# SCH_n2_power_distribution_board-png_2022.net
KiCad netlist of a schematic drawn in EasyEDA
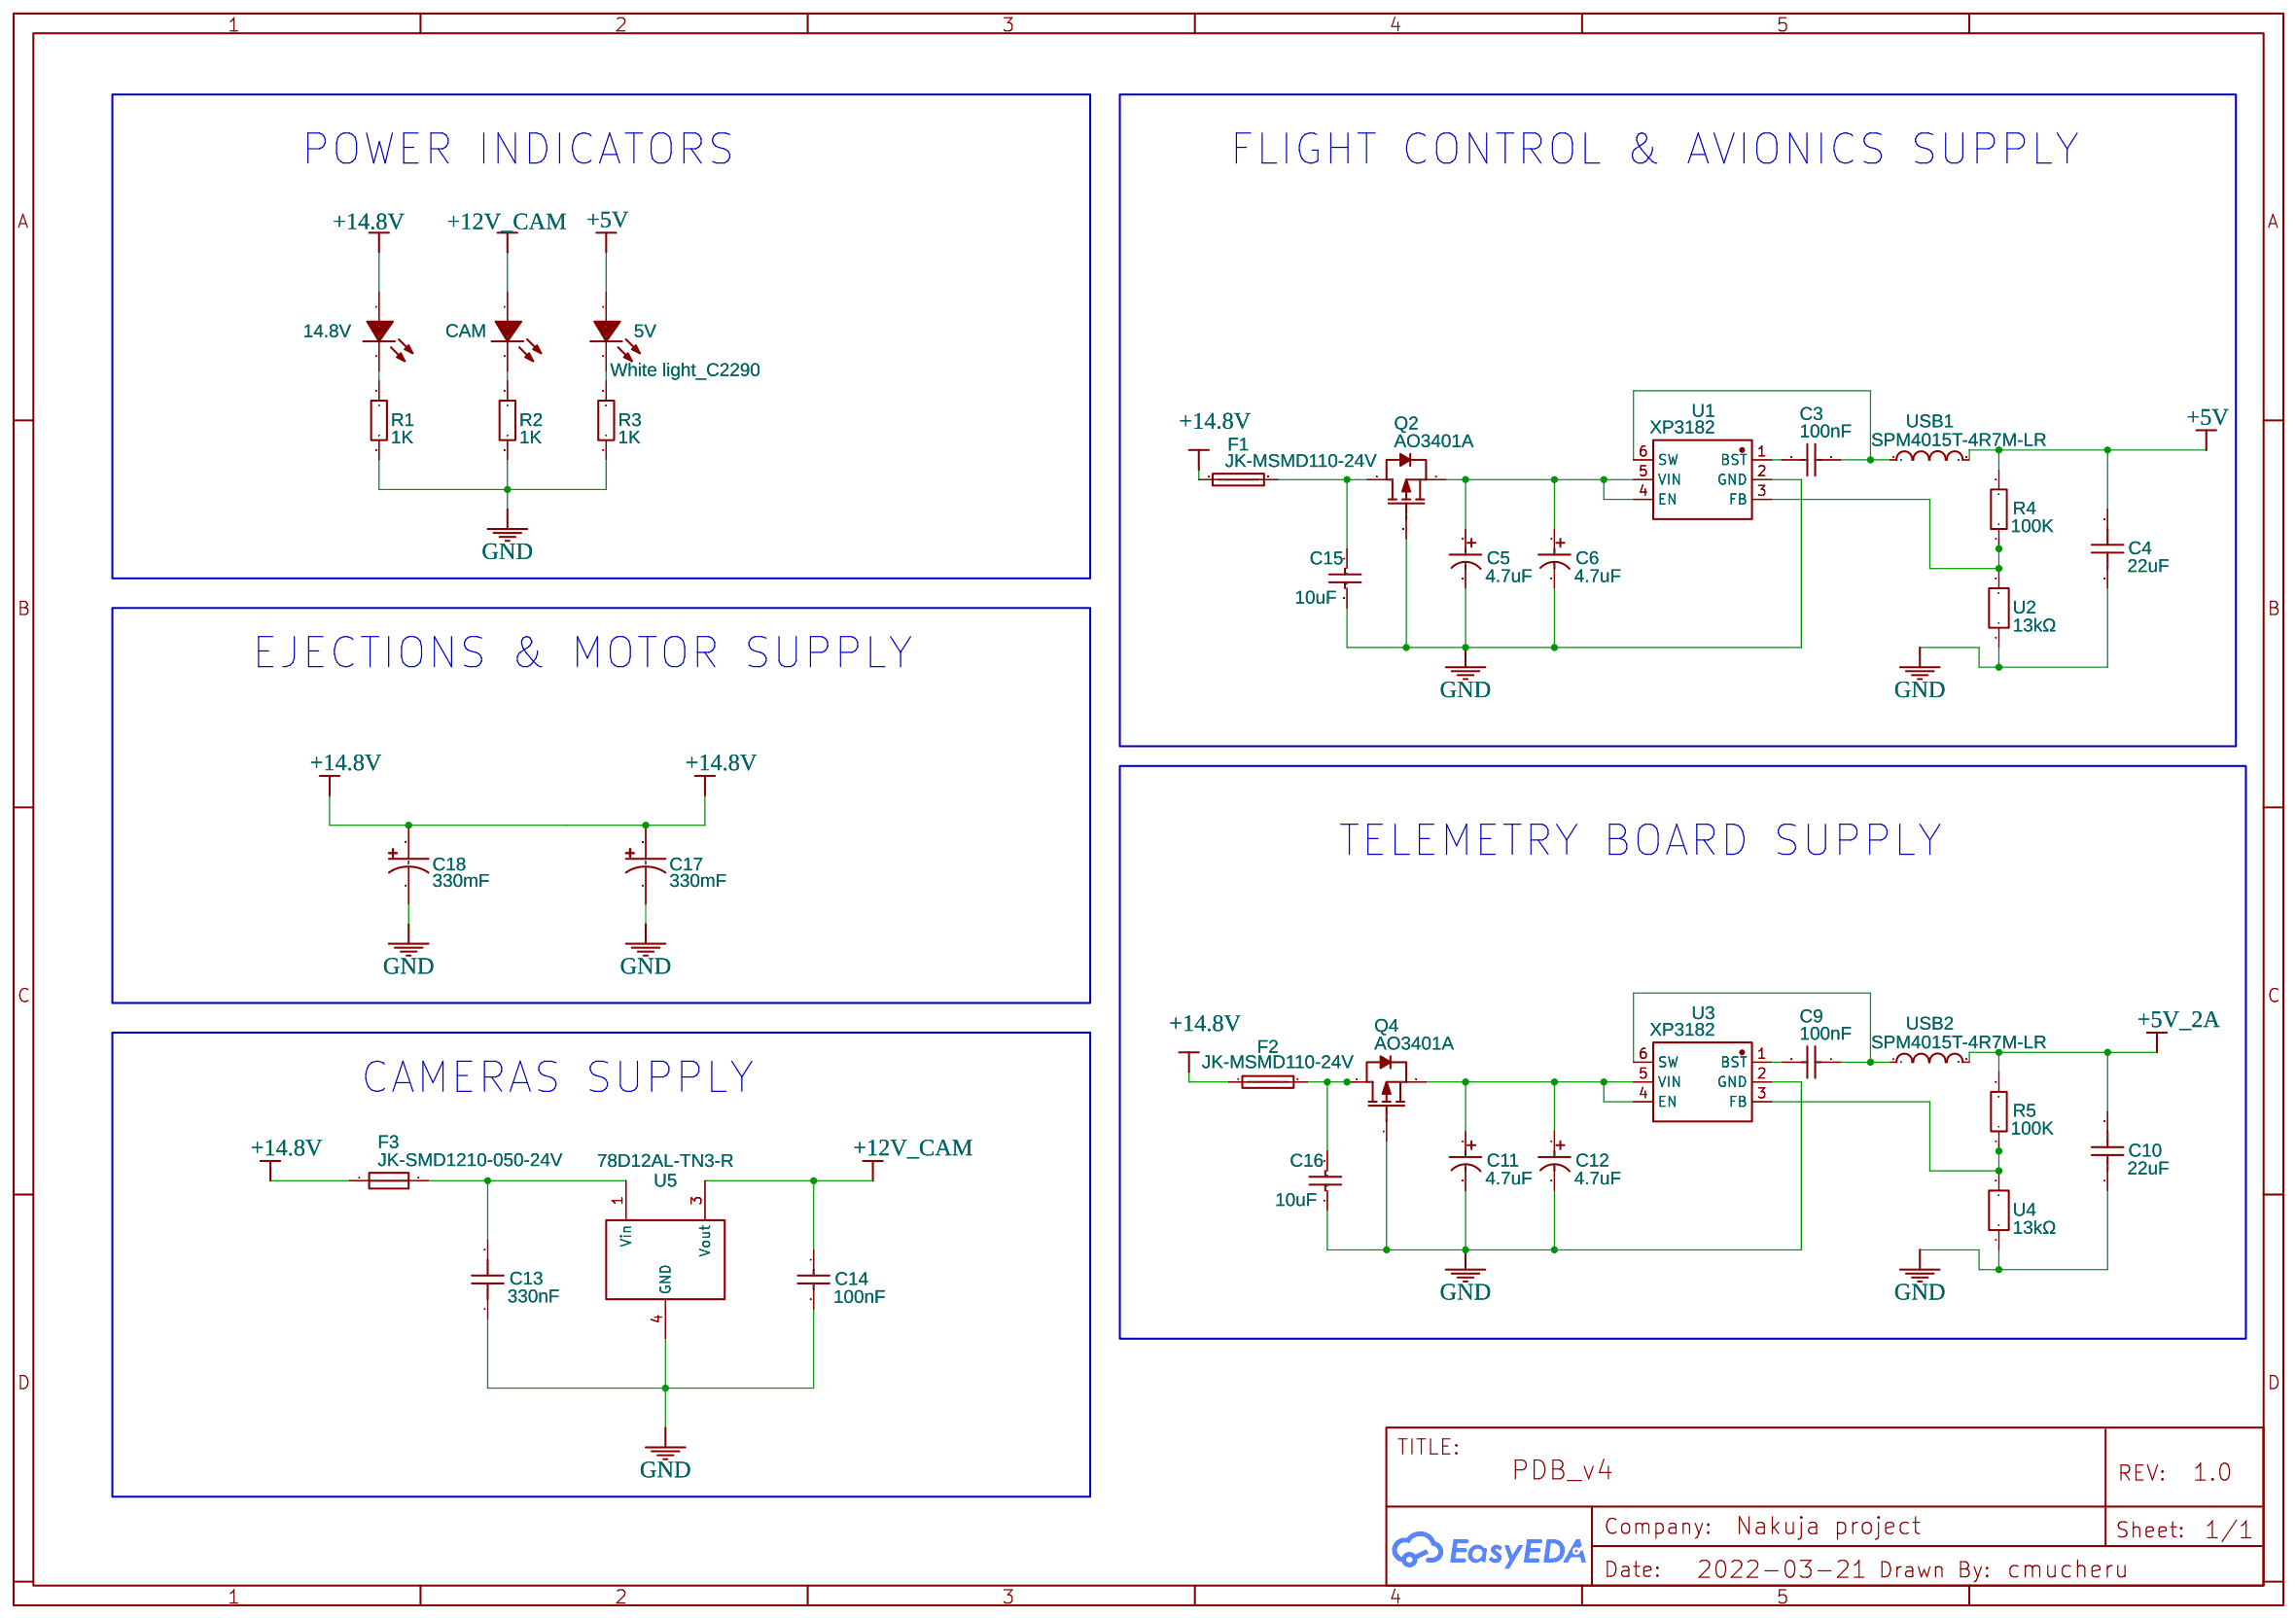
[diagram p0: PDB]
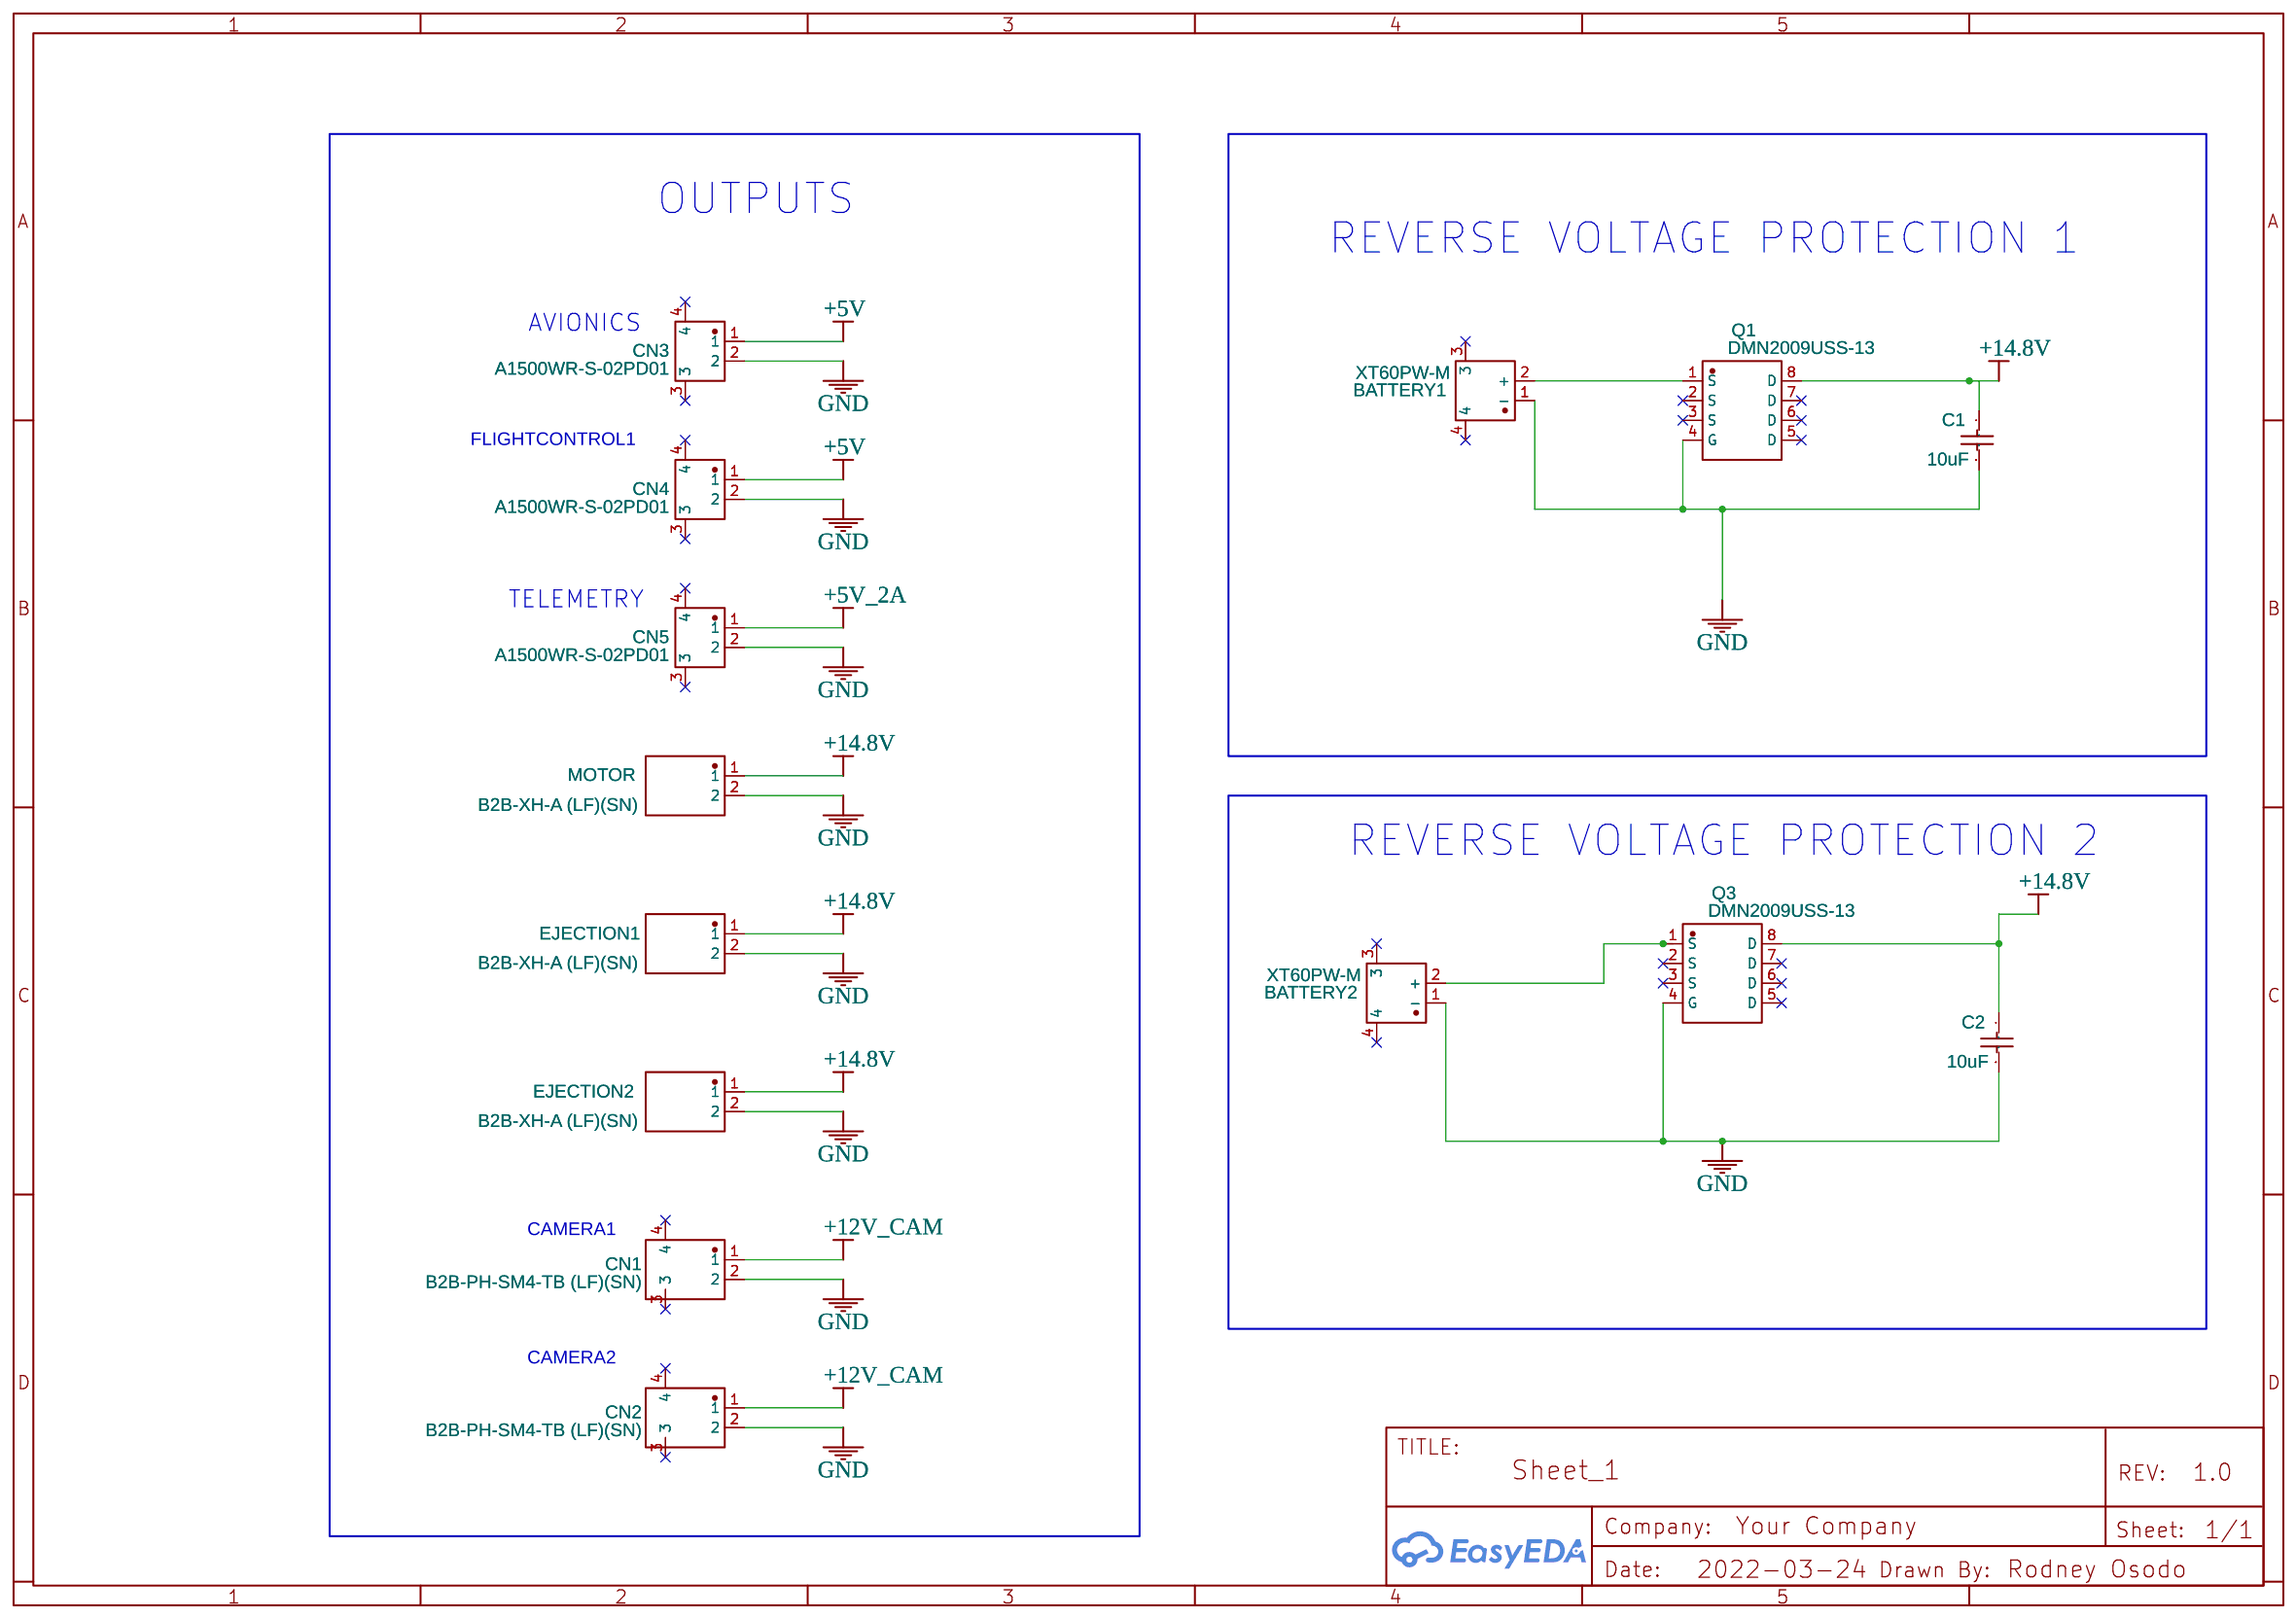
[diagram p1: Connectors]

(export (version "E")
  (design (tool "Eeschema 10.0.6"))
  (components
    (comp (ref "5V")
      (value "White light_C2290")
      (fields
        (field (name "BOM_Manufacturer Part") "0603White light")
        (field (name "BOM_Supplier Part") "C2290")
      )
      (libsource (lib "") (part "0603White light_C2290_1"))
    )
    (comp (ref "14.8V")
      (value "White light_C2290")
      (fields
        (field (name "BOM_Manufacturer Part") "0603White light")
        (field (name "BOM_Supplier Part") "C2290")
      )
      (libsource (lib "") (part "0603White light_C2290"))
    )
    (comp (ref "C3")
      (value "100nF")
      (fields
        (field (name "BOM_Manufacturer Part") "CL05B104KO5NNNC")
        (field (name "BOM_Supplier Part") "C1525")
      )
      (libsource (lib "") (part "CL05B104KO5NNNC_1"))
    )
    (comp (ref "C4")
      (value "22uF")
      (fields
        (field (name "BOM_Manufacturer Part") "GRM155R60J226ME11D")
        (field (name "BOM_Supplier Part") "C415703")
      )
      (libsource (lib "") (part "GRM155R60J226ME11D"))
    )
    (comp (ref "C5")
      (value "4.7uF")
      (fields
        (field (name "BOM_Manufacturer Part") "RVT1V4R7M0405")
        (field (name "BOM_Supplier Part") "C72511")
      )
      (libsource (lib "") (part "RVT1V4R7M0405"))
    )
    (comp (ref "C6")
      (value "4.7uF")
      (fields
        (field (name "BOM_Manufacturer Part") "RVT1V4R7M0405")
        (field (name "BOM_Supplier Part") "C72511")
      )
      (libsource (lib "") (part "RVT1V4R7M0405"))
    )
    (comp (ref "C9")
      (value "100nF")
      (fields
        (field (name "BOM_Manufacturer Part") "CL05B104KO5NNNC")
        (field (name "BOM_Supplier Part") "C1525")
      )
      (libsource (lib "") (part "CL05B104KO5NNNC_1"))
    )
    (comp (ref "C10")
      (value "22uF")
      (fields
        (field (name "BOM_Manufacturer Part") "GRM155R60J226ME11D")
        (field (name "BOM_Supplier Part") "C415703")
      )
      (libsource (lib "") (part "GRM155R60J226ME11D"))
    )
    (comp (ref "C11")
      (value "4.7uF")
      (fields
        (field (name "BOM_Manufacturer Part") "RVT1V4R7M0405")
        (field (name "BOM_Supplier Part") "C72511")
      )
      (libsource (lib "") (part "RVT1V4R7M0405"))
    )
    (comp (ref "C12")
      (value "4.7uF")
      (fields
        (field (name "BOM_Manufacturer Part") "RVT1V4R7M0405")
        (field (name "BOM_Supplier Part") "C72511")
      )
      (libsource (lib "") (part "RVT1V4R7M0405"))
    )
    (comp (ref "C13")
      (value "330nF")
      (fields
        (field (name "BOM_Manufacturer Part") "CC0402ZRY5V7BB334")
        (field (name "BOM_Supplier Part") "C527033")
      )
      (libsource (lib "") (part "CC0402ZRY5V7BB334"))
    )
    (comp (ref "C14")
      (value "100nF")
      (fields
        (field (name "BOM_Manufacturer Part") "CL05B104KO5NNNC")
        (field (name "BOM_Supplier Part") "C1525")
      )
      (libsource (lib "") (part "CL05B104KO5NNNC"))
    )
    (comp (ref "C15")
      (value "10uF")
      (fields
        (field (name "BOM_Manufacturer Part") "CL05A106MQ5NUNC")
        (field (name "BOM_Supplier Part") "C15525")
      )
      (libsource (lib "") (part "CL05A106MQ5NUNC"))
    )
    (comp (ref "C16")
      (value "10uF")
      (fields
        (field (name "BOM_Manufacturer Part") "CL05A106MQ5NUNC")
        (field (name "BOM_Supplier Part") "C15525")
      )
      (libsource (lib "") (part "CL05A106MQ5NUNC"))
    )
    (comp (ref "C17")
      (value "330mF")
      (fields
        (field (name "BOM_Manufacturer Part") "EECS0HD334H")
        (field (name "BOM_Supplier Part") "C128528")
      )
      (libsource (lib "") (part "EECS0HD334H_1"))
    )
    (comp (ref "C18")
      (value "330mF")
      (fields
        (field (name "BOM_Manufacturer Part") "EECS0HD334H")
        (field (name "BOM_Supplier Part") "C128528")
      )
      (libsource (lib "") (part "EECS0HD334H"))
    )
    (comp (ref "CAM")
      (value "White light_C2290")
      (fields
        (field (name "BOM_Manufacturer Part") "0603White light")
        (field (name "BOM_Supplier Part") "C2290")
      )
      (libsource (lib "") (part "0603White light_C2290_2"))
    )
    (comp (ref "F1")
      (value "JK-MSMD110-24V")
      (fields (field (name "BOM_Supplier Part") "C369172"))
      (libsource (lib "") (part "JK-MSMD110-24V"))
    )
    (comp (ref "F2")
      (value "JK-MSMD110-24V")
      (fields (field (name "BOM_Supplier Part") "C369172"))
      (libsource (lib "") (part "JK-MSMD110-24V"))
    )
    (comp (ref "F3")
      (value "JK-SMD1210-050-24V")
      (fields (field (name "BOM_Supplier Part") "C720078"))
      (libsource (lib "") (part "JK-SMD1210-050-24V"))
    )
    (comp (ref "Q2")
      (value "AO3401A")
      (fields (field (name "BOM_Supplier Part") "C15127"))
      (libsource (lib "") (part "AO3401A"))
    )
    (comp (ref "Q4")
      (value "AO3401A")
      (fields (field (name "BOM_Supplier Part") "C15127"))
      (libsource (lib "") (part "AO3401A"))
    )
    (comp (ref "R1")
      (value "1K")
      (fields
        (field (name "BOM_Manufacturer Part") "0402WGF5101TCE")
        (field (name "BOM_Supplier Part") "C25905")
      )
      (libsource (lib "") (part "0402WGF5101TCE"))
    )
    (comp (ref "R2")
      (value "1K")
      (fields
        (field (name "BOM_Manufacturer Part") "0402WGF5101TCE")
        (field (name "BOM_Supplier Part") "C25905")
      )
      (libsource (lib "") (part "0402WGF5101TCE"))
    )
    (comp (ref "R3")
      (value "1K")
      (fields
        (field (name "BOM_Manufacturer Part") "0402WGF5101TCE")
        (field (name "BOM_Supplier Part") "C25905")
      )
      (libsource (lib "") (part "0402WGF5101TCE_1"))
    )
    (comp (ref "R4")
      (value "100K")
      (fields
        (field (name "BOM_Manufacturer Part") "0402WGF1003TCE")
        (field (name "BOM_Supplier Part") "C25741")
      )
      (libsource (lib "") (part "0402WGF1003TCE"))
    )
    (comp (ref "R5")
      (value "100K")
      (fields
        (field (name "BOM_Manufacturer Part") "0402WGF1003TCE")
        (field (name "BOM_Supplier Part") "C25741")
      )
      (libsource (lib "") (part "0402WGF1003TCE"))
    )
    (comp (ref "U1")
      (value "XP3182")
      (fields (field (name "BOM_Supplier Part") "C2802261"))
      (libsource (lib "") (part "XP3182"))
    )
    (comp (ref "U2")
      (value "13kΩ")
      (fields
        (field (name "BOM_Manufacturer Part") "PTFR0402B13K0P9")
        (field (name "BOM_Supplier Part") "C2693072")
      )
      (libsource (lib "") (part "PTFR0402B13K0P9"))
    )
    (comp (ref "U3")
      (value "XP3182")
      (fields (field (name "BOM_Supplier Part") "C2802261"))
      (libsource (lib "") (part "XP3182"))
    )
    (comp (ref "U4")
      (value "13kΩ")
      (fields
        (field (name "BOM_Manufacturer Part") "PTFR0402B13K0P9")
        (field (name "BOM_Supplier Part") "C2693072")
      )
      (libsource (lib "") (part "PTFR0402B13K0P9"))
    )
    (comp (ref "U5")
      (value "78D12AL-TN3-R")
      (fields (field (name "BOM_Supplier Part") "C73290"))
      (libsource (lib "") (part "78D12AL-TN3-R"))
    )
    (comp (ref "USB1")
      (value "SPM4015T-4R7M-LR")
      (fields (field (name "BOM_Supplier Part") "C2052599"))
      (libsource (lib "") (part "SPM4015T-4R7M-LR"))
    )
    (comp (ref "USB2")
      (value "SPM4015T-4R7M-LR")
      (fields (field (name "BOM_Supplier Part") "C2052599"))
      (libsource (lib "") (part "SPM4015T-4R7M-LR"))
    )
    (comp (ref "BATTERY1")
      (value "XT60PW-M")
      (fields (field (name "BOM_Supplier Part") "C98732"))
      (libsource (lib "") (part "XT60PW-M"))
    )
    (comp (ref "BATTERY2")
      (value "XT60PW-M")
      (fields (field (name "BOM_Supplier Part") "C98732"))
      (libsource (lib "") (part "XT60PW-M"))
    )
    (comp (ref "C1")
      (value "10uF")
      (fields
        (field (name "BOM_Manufacturer Part") "CL05A106MQ5NUNC")
        (field (name "BOM_Supplier Part") "C15525")
      )
      (libsource (lib "") (part "CL05A106MQ5NUNC"))
    )
    (comp (ref "C2")
      (value "10uF")
      (fields
        (field (name "BOM_Manufacturer Part") "CL05A106MQ5NUNC")
        (field (name "BOM_Supplier Part") "C15525")
      )
      (libsource (lib "") (part "CL05A106MQ5NUNC"))
    )
    (comp (ref "CN1")
      (value "B2B-PH-SM4-TB (LF)(SN)")
      (fields (field (name "BOM_Supplier Part") "C160352"))
      (libsource (lib "") (part "B2B-PH-SM4-TB (LF)(SN)"))
    )
    (comp (ref "CN2")
      (value "B2B-PH-SM4-TB (LF)(SN)")
      (fields (field (name "BOM_Supplier Part") "C160352"))
      (libsource (lib "") (part "B2B-PH-SM4-TB (LF)(SN)"))
    )
    (comp (ref "CN3")
      (value "A1500WR-S-02PD01")
      (fields (field (name "BOM_Supplier Part") "C360106"))
      (libsource (lib "") (part "A1500WR-S-02PD01"))
    )
    (comp (ref "CN4")
      (value "A1500WR-S-02PD01")
      (fields (field (name "BOM_Supplier Part") "C360106"))
      (libsource (lib "") (part "A1500WR-S-02PD01"))
    )
    (comp (ref "CN5")
      (value "A1500WR-S-02PD01")
      (fields (field (name "BOM_Supplier Part") "C360106"))
      (libsource (lib "") (part "A1500WR-S-02PD01"))
    )
    (comp (ref "EJECTION1")
      (value "B2B-XH-A (LF)(SN)")
      (fields (field (name "BOM_Supplier Part") "C158012"))
      (libsource (lib "") (part "B2B-XH-A (LF)(SN)"))
    )
    (comp (ref "EJECTION2")
      (value "B2B-XH-A (LF)(SN)")
      (fields (field (name "BOM_Supplier Part") "C158012"))
      (libsource (lib "") (part "B2B-XH-A (LF)(SN)"))
    )
    (comp (ref "MOTOR")
      (value "B2B-XH-A (LF)(SN)")
      (fields (field (name "BOM_Supplier Part") "C158012"))
      (libsource (lib "") (part "B2B-XH-A (LF)(SN)_1"))
    )
    (comp (ref "Q1")
      (value "DMN2009USS-13")
      (fields (field (name "BOM_Supplier Part") "C460995"))
      (libsource (lib "") (part "DMN2009USS-13"))
    )
    (comp (ref "Q3")
      (value "DMN2009USS-13")
      (fields (field (name "BOM_Supplier Part") "C460995"))
      (libsource (lib "") (part "DMN2009USS-13"))
    )
  )
  (nets
    (net (code "1") (name "+5V") (class "Default")
      (node (ref "5V") (pin "1") (pinfunction "A_1") (pintype "unspecified"))
      (node (ref "C4") (pin "2") (pinfunction "2_2") (pintype "unspecified"))
      (node (ref "CN3") (pin "1") (pinfunction "1_1") (pintype "unspecified"))
      (node (ref "CN4") (pin "1") (pinfunction "1_1") (pintype "unspecified"))
      (node (ref "R4") (pin "2") (pinfunction "2_2") (pintype "input"))
      (node (ref "USB1") (pin "2") (pinfunction "2_2") (pintype "unspecified"))
    )
    (net (code "2") (name "+5V_2A") (class "Default")
      (node (ref "C10") (pin "2") (pinfunction "2_2") (pintype "unspecified"))
      (node (ref "CN5") (pin "1") (pinfunction "1_1") (pintype "unspecified"))
      (node (ref "R5") (pin "2") (pinfunction "2_2") (pintype "input"))
      (node (ref "USB2") (pin "2") (pinfunction "2_2") (pintype "unspecified"))
    )
    (net (code "3") (name "+12V_CAM") (class "Default")
      (node (ref "C14") (pin "1") (pinfunction "1_1") (pintype "input"))
      (node (ref "CAM") (pin "1") (pinfunction "A_1") (pintype "unspecified"))
      (node (ref "CN1") (pin "1") (pinfunction "1_1") (pintype "unspecified"))
      (node (ref "CN2") (pin "1") (pinfunction "1_1") (pintype "unspecified"))
      (node (ref "U5") (pin "3") (pinfunction "Vout_3") (pintype "unspecified"))
    )
    (net (code "4") (name "+14.8V") (class "Default")
      (node (ref "14.8V") (pin "1") (pinfunction "A_1") (pintype "unspecified"))
      (node (ref "C1") (pin "1") (pinfunction "1_1") (pintype "input"))
      (node (ref "C17") (pin "1") (pinfunction "1_1") (pintype "unspecified"))
      (node (ref "C18") (pin "1") (pinfunction "1_1") (pintype "unspecified"))
      (node (ref "C2") (pin "1") (pinfunction "1_1") (pintype "input"))
      (node (ref "EJECTION1") (pin "1") (pinfunction "1_1") (pintype "unspecified"))
      (node (ref "EJECTION2") (pin "1") (pinfunction "1_1") (pintype "unspecified"))
      (node (ref "F1") (pin "1") (pinfunction "1_1") (pintype "unspecified"))
      (node (ref "F2") (pin "1") (pinfunction "1_1") (pintype "unspecified"))
      (node (ref "F3") (pin "1") (pinfunction "1_1") (pintype "unspecified"))
      (node (ref "MOTOR") (pin "1") (pinfunction "1_1") (pintype "unspecified"))
      (node (ref "Q1") (pin "8") (pinfunction "D_8") (pintype "unspecified"))
      (node (ref "Q3") (pin "8") (pinfunction "D_8") (pintype "unspecified"))
    )
    (net (code "5") (name "GND") (class "Default")
      (node (ref "BATTERY1") (pin "1") (pinfunction "-_1") (pintype "unspecified"))
      (node (ref "BATTERY2") (pin "1") (pinfunction "-_1") (pintype "unspecified"))
      (node (ref "C1") (pin "2") (pinfunction "2_2") (pintype "input"))
      (node (ref "C10") (pin "1") (pinfunction "1_1") (pintype "unspecified"))
      (node (ref "C11") (pin "2") (pinfunction "2_2") (pintype "input"))
      (node (ref "C12") (pin "2") (pinfunction "2_2") (pintype "input"))
      (node (ref "C13") (pin "1") (pinfunction "1_1") (pintype "unspecified"))
      (node (ref "C14") (pin "2") (pinfunction "2_2") (pintype "input"))
      (node (ref "C15") (pin "2") (pinfunction "2_2") (pintype "input"))
      (node (ref "C16") (pin "2") (pinfunction "2_2") (pintype "input"))
      (node (ref "C17") (pin "2") (pinfunction "2_2") (pintype "unspecified"))
      (node (ref "C18") (pin "2") (pinfunction "2_2") (pintype "unspecified"))
      (node (ref "C2") (pin "2") (pinfunction "2_2") (pintype "input"))
      (node (ref "C4") (pin "1") (pinfunction "1_1") (pintype "unspecified"))
      (node (ref "C5") (pin "2") (pinfunction "2_2") (pintype "input"))
      (node (ref "C6") (pin "2") (pinfunction "2_2") (pintype "input"))
      (node (ref "CN1") (pin "2") (pinfunction "2_2") (pintype "unspecified"))
      (node (ref "CN2") (pin "2") (pinfunction "2_2") (pintype "unspecified"))
      (node (ref "CN3") (pin "2") (pinfunction "2_2") (pintype "unspecified"))
      (node (ref "CN4") (pin "2") (pinfunction "2_2") (pintype "unspecified"))
      (node (ref "CN5") (pin "2") (pinfunction "2_2") (pintype "unspecified"))
      (node (ref "EJECTION1") (pin "2") (pinfunction "2_2") (pintype "unspecified"))
      (node (ref "EJECTION2") (pin "2") (pinfunction "2_2") (pintype "unspecified"))
      (node (ref "MOTOR") (pin "2") (pinfunction "2_2") (pintype "unspecified"))
      (node (ref "Q1") (pin "4") (pinfunction "G_4") (pintype "unspecified"))
      (node (ref "Q2") (pin "1") (pinfunction "G_1") (pintype "unspecified"))
      (node (ref "Q3") (pin "4") (pinfunction "G_4") (pintype "unspecified"))
      (node (ref "Q4") (pin "1") (pinfunction "G_1") (pintype "unspecified"))
      (node (ref "R1") (pin "2") (pinfunction "2_2") (pintype "input"))
      (node (ref "R2") (pin "2") (pinfunction "2_2") (pintype "input"))
      (node (ref "R3") (pin "1") (pinfunction "1_1") (pintype "input"))
      (node (ref "U1") (pin "2") (pinfunction "GND_2") (pintype "unspecified"))
      (node (ref "U2") (pin "1") (pinfunction "1_1") (pintype "unspecified"))
      (node (ref "U3") (pin "2") (pinfunction "GND_2") (pintype "unspecified"))
      (node (ref "U4") (pin "1") (pinfunction "1_1") (pintype "unspecified"))
      (node (ref "U5") (pin "4") (pinfunction "GND_4") (pintype "unspecified"))
    )
    (net (code "6") (name "Net-(5V-K)") (class "Default")
      (node (ref "5V") (pin "2") (pinfunction "K_2") (pintype "unspecified"))
      (node (ref "R3") (pin "2") (pinfunction "2_2") (pintype "input"))
    )
    (net (code "7") (name "Net-(14.8V-K)") (class "Default")
      (node (ref "14.8V") (pin "2") (pinfunction "K_2") (pintype "unspecified"))
      (node (ref "R1") (pin "1") (pinfunction "1_1") (pintype "input"))
    )
    (net (code "8") (name "Net-(BATTERY1-+)") (class "Default")
      (node (ref "BATTERY1") (pin "2") (pinfunction "+_2") (pintype "unspecified"))
      (node (ref "Q1") (pin "1") (pinfunction "S_1") (pintype "unspecified"))
    )
    (net (code "9") (name "Net-(BATTERY2-+)") (class "Default")
      (node (ref "BATTERY2") (pin "2") (pinfunction "+_2") (pintype "unspecified"))
      (node (ref "Q3") (pin "1") (pinfunction "S_1") (pintype "unspecified"))
    )
    (net (code "10") (name "Net-(CAM-K)") (class "Default")
      (node (ref "CAM") (pin "2") (pinfunction "K_2") (pintype "unspecified"))
      (node (ref "R2") (pin "1") (pinfunction "1_1") (pintype "input"))
    )
    (net (code "11") (name "Net-(Q2-D)") (class "Default")
      (node (ref "C15") (pin "1") (pinfunction "1_1") (pintype "input"))
      (node (ref "F1") (pin "2") (pinfunction "2_2") (pintype "unspecified"))
      (node (ref "Q2") (pin "3") (pinfunction "D_3") (pintype "unspecified"))
    )
    (net (code "12") (name "Net-(Q2-S)") (class "Default")
      (node (ref "C5") (pin "1") (pinfunction "1_1") (pintype "input"))
      (node (ref "C6") (pin "1") (pinfunction "1_1") (pintype "input"))
      (node (ref "Q2") (pin "2") (pinfunction "S_2") (pintype "unspecified"))
      (node (ref "U1") (pin "4") (pinfunction "EN_4") (pintype "unspecified"))
      (node (ref "U1") (pin "5") (pinfunction "VIN_5") (pintype "unspecified"))
    )
    (net (code "13") (name "Net-(Q4-D)") (class "Default")
      (node (ref "C16") (pin "1") (pinfunction "1_1") (pintype "input"))
      (node (ref "F2") (pin "2") (pinfunction "2_2") (pintype "unspecified"))
      (node (ref "Q4") (pin "3") (pinfunction "D_3") (pintype "unspecified"))
    )
    (net (code "14") (name "Net-(Q4-S)") (class "Default")
      (node (ref "C11") (pin "1") (pinfunction "1_1") (pintype "input"))
      (node (ref "C12") (pin "1") (pinfunction "1_1") (pintype "input"))
      (node (ref "Q4") (pin "2") (pinfunction "S_2") (pintype "unspecified"))
      (node (ref "U3") (pin "4") (pinfunction "EN_4") (pintype "unspecified"))
      (node (ref "U3") (pin "5") (pinfunction "VIN_5") (pintype "unspecified"))
    )
    (net (code "15") (name "Net-(U1-BST)") (class "Default")
      (node (ref "C3") (pin "2") (pinfunction "2_2") (pintype "input"))
      (node (ref "U1") (pin "1") (pinfunction "BST_1") (pintype "unspecified"))
    )
    (net (code "16") (name "Net-(U1-FB)") (class "Default")
      (node (ref "R4") (pin "1") (pinfunction "1_1") (pintype "input"))
      (node (ref "U1") (pin "3") (pinfunction "FB_3") (pintype "unspecified"))
      (node (ref "U2") (pin "2") (pinfunction "2_2") (pintype "unspecified"))
    )
    (net (code "17") (name "Net-(U1-SW)") (class "Default")
      (node (ref "C3") (pin "1") (pinfunction "1_1") (pintype "input"))
      (node (ref "U1") (pin "6") (pinfunction "SW_6") (pintype "unspecified"))
      (node (ref "USB1") (pin "1") (pinfunction "1_1") (pintype "unspecified"))
    )
    (net (code "18") (name "Net-(U3-BST)") (class "Default")
      (node (ref "C9") (pin "2") (pinfunction "2_2") (pintype "input"))
      (node (ref "U3") (pin "1") (pinfunction "BST_1") (pintype "unspecified"))
    )
    (net (code "19") (name "Net-(U3-FB)") (class "Default")
      (node (ref "R5") (pin "1") (pinfunction "1_1") (pintype "input"))
      (node (ref "U3") (pin "3") (pinfunction "FB_3") (pintype "unspecified"))
      (node (ref "U4") (pin "2") (pinfunction "2_2") (pintype "unspecified"))
    )
    (net (code "20") (name "Net-(U3-SW)") (class "Default")
      (node (ref "C9") (pin "1") (pinfunction "1_1") (pintype "input"))
      (node (ref "U3") (pin "6") (pinfunction "SW_6") (pintype "unspecified"))
      (node (ref "USB2") (pin "1") (pinfunction "1_1") (pintype "unspecified"))
    )
    (net (code "21") (name "Net-(U5-Vin)") (class "Default")
      (node (ref "C13") (pin "2") (pinfunction "2_2") (pintype "unspecified"))
      (node (ref "F3") (pin "2") (pinfunction "2_2") (pintype "unspecified"))
      (node (ref "U5") (pin "1") (pinfunction "Vin_1") (pintype "unspecified"))
    )
    (net (code "22") (name "unconnected-(BATTERY1-Pad3)") (class "Default")
      (node (ref "BATTERY1") (pin "3") (pinfunction "3_3") (pintype "unspecified+no_connect"))
    )
    (net (code "23") (name "unconnected-(BATTERY1-Pad4)") (class "Default")
      (node (ref "BATTERY1") (pin "4") (pinfunction "4_4") (pintype "unspecified+no_connect"))
    )
    (net (code "24") (name "unconnected-(BATTERY2-Pad3)") (class "Default")
      (node (ref "BATTERY2") (pin "3") (pinfunction "3_3") (pintype "unspecified+no_connect"))
    )
    (net (code "25") (name "unconnected-(BATTERY2-Pad4)") (class "Default")
      (node (ref "BATTERY2") (pin "4") (pinfunction "4_4") (pintype "unspecified+no_connect"))
    )
    (net (code "26") (name "unconnected-(CN1-Pad3)") (class "Default")
      (node (ref "CN1") (pin "3") (pinfunction "3_3") (pintype "unspecified+no_connect"))
    )
    (net (code "27") (name "unconnected-(CN1-Pad4)") (class "Default")
      (node (ref "CN1") (pin "4") (pinfunction "4_4") (pintype "unspecified+no_connect"))
    )
    (net (code "28") (name "unconnected-(CN2-Pad3)") (class "Default")
      (node (ref "CN2") (pin "3") (pinfunction "3_3") (pintype "unspecified+no_connect"))
    )
    (net (code "29") (name "unconnected-(CN2-Pad4)") (class "Default")
      (node (ref "CN2") (pin "4") (pinfunction "4_4") (pintype "unspecified+no_connect"))
    )
    (net (code "30") (name "unconnected-(CN3-Pad3)") (class "Default")
      (node (ref "CN3") (pin "3") (pinfunction "3_3") (pintype "unspecified+no_connect"))
    )
    (net (code "31") (name "unconnected-(CN3-Pad4)") (class "Default")
      (node (ref "CN3") (pin "4") (pinfunction "4_4") (pintype "unspecified+no_connect"))
    )
    (net (code "32") (name "unconnected-(CN4-Pad3)") (class "Default")
      (node (ref "CN4") (pin "3") (pinfunction "3_3") (pintype "unspecified+no_connect"))
    )
    (net (code "33") (name "unconnected-(CN4-Pad4)") (class "Default")
      (node (ref "CN4") (pin "4") (pinfunction "4_4") (pintype "unspecified+no_connect"))
    )
    (net (code "34") (name "unconnected-(CN5-Pad3)") (class "Default")
      (node (ref "CN5") (pin "3") (pinfunction "3_3") (pintype "unspecified+no_connect"))
    )
    (net (code "35") (name "unconnected-(CN5-Pad4)") (class "Default")
      (node (ref "CN5") (pin "4") (pinfunction "4_4") (pintype "unspecified+no_connect"))
    )
    (net (code "36") (name "unconnected-(Q1-D-Pad5)") (class "Default")
      (node (ref "Q1") (pin "5") (pinfunction "D_5") (pintype "unspecified+no_connect"))
    )
    (net (code "37") (name "unconnected-(Q1-D-Pad6)") (class "Default")
      (node (ref "Q1") (pin "6") (pinfunction "D_6") (pintype "unspecified+no_connect"))
    )
    (net (code "38") (name "unconnected-(Q1-D-Pad7)") (class "Default")
      (node (ref "Q1") (pin "7") (pinfunction "D_7") (pintype "unspecified+no_connect"))
    )
    (net (code "39") (name "unconnected-(Q1-S-Pad2)") (class "Default")
      (node (ref "Q1") (pin "2") (pinfunction "S_2") (pintype "unspecified+no_connect"))
    )
    (net (code "40") (name "unconnected-(Q1-S-Pad3)") (class "Default")
      (node (ref "Q1") (pin "3") (pinfunction "S_3") (pintype "unspecified+no_connect"))
    )
    (net (code "41") (name "unconnected-(Q3-D-Pad5)") (class "Default")
      (node (ref "Q3") (pin "5") (pinfunction "D_5") (pintype "unspecified+no_connect"))
    )
    (net (code "42") (name "unconnected-(Q3-D-Pad6)") (class "Default")
      (node (ref "Q3") (pin "6") (pinfunction "D_6") (pintype "unspecified+no_connect"))
    )
    (net (code "43") (name "unconnected-(Q3-D-Pad7)") (class "Default")
      (node (ref "Q3") (pin "7") (pinfunction "D_7") (pintype "unspecified+no_connect"))
    )
    (net (code "44") (name "unconnected-(Q3-S-Pad2)") (class "Default")
      (node (ref "Q3") (pin "2") (pinfunction "S_2") (pintype "unspecified+no_connect"))
    )
    (net (code "45") (name "unconnected-(Q3-S-Pad3)") (class "Default")
      (node (ref "Q3") (pin "3") (pinfunction "S_3") (pintype "unspecified+no_connect"))
    )
  )
)
